# Headphone-Amplifier-ClassAB-alt5.net
KiCad netlist of a schematic drawn in EAGLE
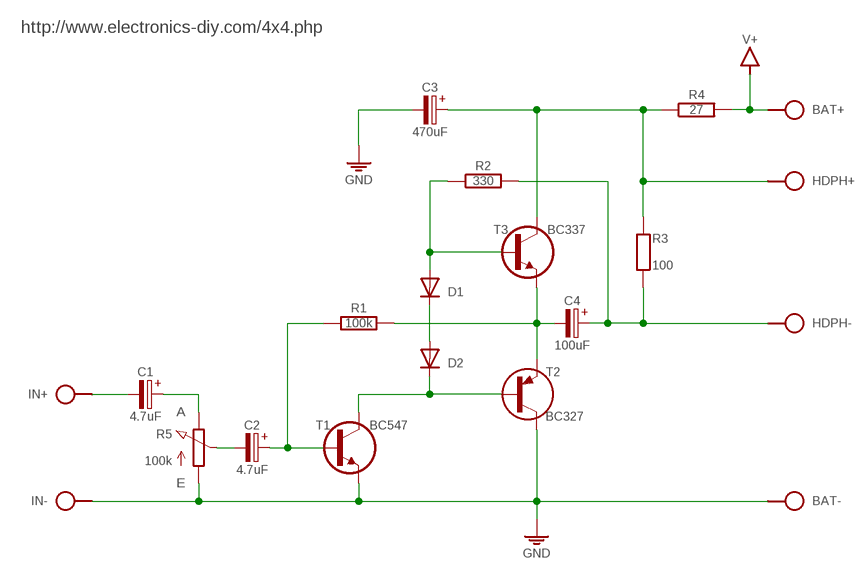
[diagram p0: schematic, sheet 1]

(export (version "E")
  (design (tool "Eeschema 10.0.6"))
  (components
    (comp (ref "BAT")
      (value "SPAD+-+-")
      (footprint "eagle-import:SPAD+-")
      (libsource (lib "eagle-import") (part "SPAD+-+-"))
    )
    (comp (ref "C1")
      (value "4.7uF")
      (footprint "eagle-import:E2.5-4_V")
      (libsource (lib "eagle-import") (part "CPOLE2,5-4/V"))
    )
    (comp (ref "C2")
      (value "4.7uF")
      (footprint "eagle-import:E2.5-4_V")
      (libsource (lib "eagle-import") (part "CPOLE2,5-4/V"))
    )
    (comp (ref "C3")
      (value "470uF")
      (footprint "eagle-import:E2,5-5_V")
      (libsource (lib "eagle-import") (part "CPOLE2,5-5/V"))
    )
    (comp (ref "C4")
      (value "100uF")
      (footprint "eagle-import:E2.5-4_V")
      (libsource (lib "eagle-import") (part "CPOLE2,5-4/V"))
    )
    (comp (ref "D1")
      (value "1N414834-2,5-A")
      (footprint "eagle-import:DO34-2,5-A")
      (libsource (lib "eagle-import") (part "1N414834-2,5-A"))
    )
    (comp (ref "D2")
      (value "1N414834-2,5-A")
      (footprint "eagle-import:DO34-2,5-A")
      (libsource (lib "eagle-import") (part "1N414834-2,5-A"))
    )
    (comp (ref "HDPH")
      (value "SPAD+-+-")
      (footprint "eagle-import:SPAD+-")
      (libsource (lib "eagle-import") (part "SPAD+-+-"))
    )
    (comp (ref "IN")
      (value "SPAD+--+")
      (footprint "eagle-import:SPAD-+")
      (libsource (lib "eagle-import") (part "SPAD+--+"))
    )
    (comp (ref "R1")
      (value "100k")
      (footprint "eagle-import:0202_10")
      (libsource (lib "eagle-import") (part "R-H0202/10"))
    )
    (comp (ref "R2")
      (value "330")
      (footprint "eagle-import:0202_2V")
      (libsource (lib "eagle-import") (part "R-H0202/2V"))
    )
    (comp (ref "R3")
      (value "100")
      (footprint "eagle-import:0202_2")
      (libsource (lib "eagle-import") (part "R0202/2"))
    )
    (comp (ref "R4")
      (value "27")
      (footprint "eagle-import:0204_2.54")
      (libsource (lib "eagle-import") (part "R-H0204/2.54"))
    )
    (comp (ref "R5")
      (value "100k")
      (footprint "eagle-import:CONN-3P")
      (libsource (lib "eagle-import") (part "POT-3P"))
    )
    (comp (ref "T1")
      (value "BC547")
      (footprint "eagle-import:TO92-CBE")
      (libsource (lib "eagle-import") (part "BC547CBE"))
    )
    (comp (ref "T2")
      (value "BC327")
      (footprint "eagle-import:TO92")
      (libsource (lib "eagle-import") (part "BC327"))
    )
    (comp (ref "T3")
      (value "BC337")
      (footprint "eagle-import:TO92-CBE")
      (libsource (lib "eagle-import") (part "BC337CBE"))
    )
  )
  (nets
    (net (code "1") (name "GND") (class "Default")
      (node (ref "BAT") (pin "1") (pinfunction "P$1_1") (pintype "passive"))
      (node (ref "C3") (pin "-") (pinfunction "-_-") (pintype "passive"))
      (node (ref "IN") (pin "1") (pinfunction "P$1_1") (pintype "passive"))
      (node (ref "R5") (pin "1") (pinfunction "A_1") (pintype "passive"))
      (node (ref "T1") (pin "E") (pinfunction "E_E") (pintype "passive"))
      (node (ref "T2") (pin "1") (pinfunction "C_1") (pintype "passive"))
    )
    (net (code "2") (name "Net-(C2-Pad+)") (class "Default")
      (node (ref "C2") (pin "+") (pinfunction "+_+") (pintype "passive"))
      (node (ref "R1") (pin "1") (pinfunction "1_1") (pintype "passive"))
      (node (ref "T1") (pin "B") (pinfunction "B_B") (pintype "passive"))
    )
    (net (code "3") (name "Net-(D1-PadA)") (class "Default")
      (node (ref "D1") (pin "A") (pinfunction "A_A") (pintype "passive"))
      (node (ref "R2") (pin "1") (pinfunction "1_1") (pintype "passive"))
      (node (ref "T3") (pin "B") (pinfunction "B_B") (pintype "passive"))
    )
    (net (code "4") (name "Net-(D1-PadC)") (class "Default")
      (node (ref "D1") (pin "C") (pinfunction "C_C") (pintype "passive"))
      (node (ref "D2") (pin "A") (pinfunction "A_A") (pintype "passive"))
    )
    (net (code "5") (name "Net-(HDPHA-P$1)") (class "Default")
      (node (ref "C3") (pin "+") (pinfunction "+_+") (pintype "passive"))
      (node (ref "HDPH") (pin "2") (pinfunction "P$1_2") (pintype "passive"))
      (node (ref "R3") (pin "1") (pinfunction "1_1") (pintype "passive"))
      (node (ref "R4") (pin "1") (pinfunction "1_1") (pintype "passive"))
      (node (ref "T3") (pin "C") (pinfunction "C_C") (pintype "passive"))
    )
    (net (code "6") (name "Net-(HDPHB-P$1)") (class "Default")
      (node (ref "C4") (pin "+") (pinfunction "+_+") (pintype "passive"))
      (node (ref "HDPH") (pin "1") (pinfunction "P$1_1") (pintype "passive"))
      (node (ref "R2") (pin "2") (pinfunction "2_2") (pintype "passive"))
      (node (ref "R3") (pin "2") (pinfunction "2_2") (pintype "passive"))
    )
    (net (code "7") (name "Net-(INA-P$1)") (class "Default")
      (node (ref "C1") (pin "-") (pinfunction "-_-") (pintype "passive"))
      (node (ref "IN") (pin "2") (pinfunction "P$1_2") (pintype "passive"))
    )
    (net (code "8") (name "Net-(R5-E)") (class "Default")
      (node (ref "C1") (pin "+") (pinfunction "+_+") (pintype "passive"))
      (node (ref "R5") (pin "3") (pinfunction "E_3") (pintype "passive"))
    )
    (net (code "9") (name "Net-(R5-S)") (class "Default")
      (node (ref "C2") (pin "-") (pinfunction "-_-") (pintype "passive"))
      (node (ref "R5") (pin "2") (pinfunction "S_2") (pintype "passive"))
    )
    (net (code "10") (name "Net-(T2-B)") (class "Default")
      (node (ref "D2") (pin "C") (pinfunction "C_C") (pintype "passive"))
      (node (ref "T1") (pin "C") (pinfunction "C_C") (pintype "passive"))
      (node (ref "T2") (pin "2") (pinfunction "B_2") (pintype "passive"))
    )
    (net (code "11") (name "Net-(T2-E)") (class "Default")
      (node (ref "C4") (pin "-") (pinfunction "-_-") (pintype "passive"))
      (node (ref "R1") (pin "2") (pinfunction "2_2") (pintype "passive"))
      (node (ref "T2") (pin "3") (pinfunction "E_3") (pintype "passive"))
      (node (ref "T3") (pin "E") (pinfunction "E_E") (pintype "passive"))
    )
    (net (code "12") (name "V+") (class "Default")
      (node (ref "BAT") (pin "2") (pinfunction "P$1_2") (pintype "passive"))
      (node (ref "R4") (pin "2") (pinfunction "2_2") (pintype "passive"))
    )
  )
)
